# LED_RGB.net
KiCad netlist of a schematic drawn in Altium Designer
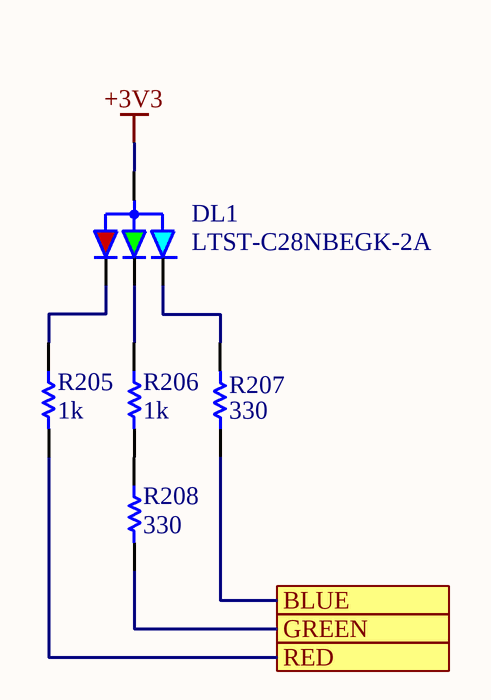
[diagram p0: LED_RGB.SchDoc]

(export (version "E")
  (design (tool "Eeschema 10.0.6"))
  (components
    (comp (ref "DL1")
      (value "LTST-C28NBEGK-2A")
      (footprint "SMLP34RGB2W")
      (description "LED RGB DIFFUSED PICOLED SMD")
      (fields (field (name "MANUFACTURER") "Liteon"))
      (libsource (lib "Clean") (part "SMLP34RGB2W3"))
    )
    (comp (ref "R205")
      (value "1k")
      (footprint "RES-0201")
      (description "RES CHIP 0201 1k 1% 1/20W")
      (fields (field (name "PART NUMBER") "RC0201FR-071KL") (field (name "TOLERANCE") "1%"))
      (libsource (lib "Clean") (part "RES"))
    )
    (comp (ref "R206")
      (value "1k")
      (footprint "RES-0201")
      (description "RES CHIP 0201 1k 1% 1/20W")
      (fields (field (name "PART NUMBER") "RC0201FR-071KL") (field (name "TOLERANCE") "1%"))
      (libsource (lib "Clean") (part "RES"))
    )
    (comp (ref "R207")
      (value "330")
      (footprint "RES-0201")
      (description "RES CHIP 0201 330R 1% 1/20W")
      (fields (field (name "MANUFACTURER") "Yageo") (field (name "POWER") "50mW"))
      (libsource (lib "Clean") (part "RES"))
    )
    (comp (ref "R208")
      (value "330")
      (footprint "RES-0201")
      (description "RES CHIP 0201 330R 1% 1/20W")
      (fields (field (name "PART NUMBER") "AC0201FR-07330RL") (field (name "TOLERANCE") "1%"))
      (libsource (lib "Clean") (part "RES"))
    )
  )
  (nets
    (net (code "1") (name "+3V3") (class "Default")
      (node (ref "DL1") (pin "1") (pinfunction "ANODE_1") (pintype "passive"))
    )
    (net (code "2") (name "/BLUE") (class "Default")
      (node (ref "R207") (pin "1") (pinfunction "1_1") (pintype "passive"))
    )
    (net (code "3") (name "/GREEN") (class "Default")
      (node (ref "R208") (pin "2") (pinfunction "2_2") (pintype "passive"))
    )
    (net (code "4") (name "/RED") (class "Default")
      (node (ref "R205") (pin "2") (pinfunction "2_2") (pintype "passive"))
    )
    (net (code "5") (name "Net-(DL1-BLUE_C)") (class "Default")
      (node (ref "DL1") (pin "3") (pinfunction "BLUE_C_3") (pintype "passive"))
      (node (ref "R207") (pin "2") (pinfunction "2_2") (pintype "passive"))
    )
    (net (code "6") (name "Net-(DL1-GREEN_C)") (class "Default")
      (node (ref "DL1") (pin "4") (pinfunction "GREEN_C_4") (pintype "passive"))
      (node (ref "R206") (pin "1") (pinfunction "1_1") (pintype "passive"))
    )
    (net (code "7") (name "Net-(DL1-RED_C)") (class "Default")
      (node (ref "DL1") (pin "2") (pinfunction "RED_C_2") (pintype "passive"))
      (node (ref "R205") (pin "1") (pinfunction "1_1") (pintype "passive"))
    )
    (net (code "8") (name "Net-(R206-Pad2)") (class "Default")
      (node (ref "R206") (pin "2") (pinfunction "2_2") (pintype "passive"))
      (node (ref "R208") (pin "1") (pinfunction "1_1") (pintype "passive"))
    )
  )
)
